# Comms.net
KiCad netlist of a schematic drawn in Altium Designer
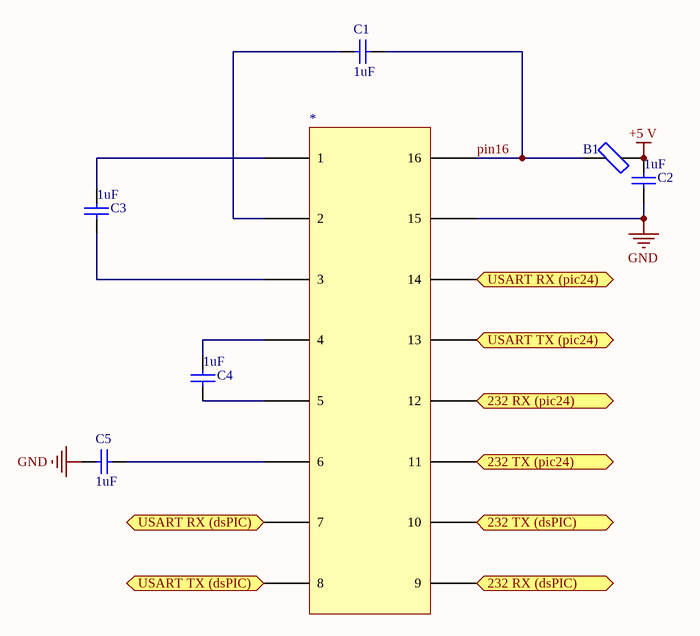
[diagram p0: Comms.SchDoc]

(export (version "E")
  (design (tool "Eeschema 10.0.6"))
  (components
    (comp (ref "*")
      (value "MAX232E")
      (footprint "SO-16_M")
      (libsource (lib "CustomParts_MattW") (part "max232"))
    )
    (comp (ref "B1")
      (value "Ferrite Bead")
      (footprint "Resistor 0603")
      (libsource (lib "PMUD") (part "Ferrite Bead"))
    )
    (comp (ref "C1")
      (value "1uF")
      (footprint "Capacitor 0603")
      (description "Capacitor (Semiconductor SIM Model)")
      (fields (field (name "Comment") "1uF Ceramic Low ESR") (field (name "PUBLISHER") "Altium Limited"))
      (libsource (lib "Miscellaneous Devices") (part "Cap Semi"))
    )
    (comp (ref "C2")
      (value "1uF")
      (footprint "Capacitor 0603")
      (description "Capacitor (Semiconductor SIM Model)")
      (fields (field (name "Comment") "1uF Ceramic Low ESR") (field (name "PUBLISHER") "Altium Limited"))
      (libsource (lib "Miscellaneous Devices") (part "Cap Semi"))
    )
    (comp (ref "C3")
      (value "1uF")
      (footprint "Capacitor 0603")
      (description "Capacitor (Semiconductor SIM Model)")
      (fields (field (name "Comment") "1uF Ceramic Low ESR") (field (name "PUBLISHER") "Altium Limited"))
      (libsource (lib "Miscellaneous Devices") (part "Cap Semi"))
    )
    (comp (ref "C4")
      (value "1uF")
      (footprint "Capacitor 0603")
      (description "Capacitor (Semiconductor SIM Model)")
      (fields (field (name "Comment") "1uF Ceramic Low ESR") (field (name "PUBLISHER") "Altium Limited"))
      (libsource (lib "Miscellaneous Devices") (part "Cap Semi"))
    )
    (comp (ref "C5")
      (value "1uF")
      (footprint "Capacitor 0603")
      (description "Capacitor (Semiconductor SIM Model)")
      (fields (field (name "Comment") "1uF Ceramic Low ESR") (field (name "PUBLISHER") "Altium Limited"))
      (libsource (lib "Miscellaneous Devices") (part "Cap Semi"))
    )
  )
  (nets
    (net (code "1") (name "+5 V") (class "Default")
      (node (ref "B1") (pin "1") (pinfunction "1_1") (pintype "passive"))
      (node (ref "C2") (pin "1") (pinfunction "1_1") (pintype "passive"))
    )
    (net (code "2") (name "/232 RX (dsPIC)") (class "Default")
      (node (ref "*") (pin "9") (pinfunction "9_9") (pintype "passive"))
    )
    (net (code "3") (name "/232 RX (pic24)") (class "Default")
      (node (ref "*") (pin "12") (pinfunction "12_12") (pintype "passive"))
    )
    (net (code "4") (name "/232 TX (dsPIC)") (class "Default")
      (node (ref "*") (pin "10") (pinfunction "10_10") (pintype "passive"))
    )
    (net (code "5") (name "/232 TX (pic24)") (class "Default")
      (node (ref "*") (pin "11") (pinfunction "11_11") (pintype "passive"))
    )
    (net (code "6") (name "/USART RX (dsPIC)") (class "Default")
      (node (ref "*") (pin "7") (pinfunction "7_7") (pintype "passive"))
    )
    (net (code "7") (name "/USART RX (pic24)") (class "Default")
      (node (ref "*") (pin "14") (pinfunction "14_14") (pintype "passive"))
    )
    (net (code "8") (name "/USART TX (dsPIC)") (class "Default")
      (node (ref "*") (pin "8") (pinfunction "8_8") (pintype "passive"))
    )
    (net (code "9") (name "/USART TX (pic24)") (class "Default")
      (node (ref "*") (pin "13") (pinfunction "13_13") (pintype "passive"))
    )
    (net (code "10") (name "/pin16") (class "Default")
      (node (ref "*") (pin "16") (pinfunction "16_16") (pintype "passive"))
      (node (ref "B1") (pin "2") (pinfunction "2_2") (pintype "passive"))
      (node (ref "C1") (pin "2") (pinfunction "2_2") (pintype "passive"))
    )
    (net (code "11") (name "GND") (class "Default")
      (node (ref "*") (pin "15") (pinfunction "15_15") (pintype "passive"))
      (node (ref "C2") (pin "2") (pinfunction "2_2") (pintype "passive"))
      (node (ref "C5") (pin "1") (pinfunction "1_1") (pintype "passive"))
    )
    (net (code "12") (name "Net-(*-Pad1)") (class "Default")
      (node (ref "*") (pin "1") (pinfunction "1_1") (pintype "passive"))
      (node (ref "C3") (pin "1") (pinfunction "1_1") (pintype "passive"))
    )
    (net (code "13") (name "Net-(*-Pad2)") (class "Default")
      (node (ref "*") (pin "2") (pinfunction "2_2") (pintype "passive"))
      (node (ref "C1") (pin "1") (pinfunction "1_1") (pintype "passive"))
    )
    (net (code "14") (name "Net-(*-Pad3)") (class "Default")
      (node (ref "*") (pin "3") (pinfunction "3_3") (pintype "passive"))
      (node (ref "C3") (pin "2") (pinfunction "2_2") (pintype "passive"))
    )
    (net (code "15") (name "Net-(*-Pad4)") (class "Default")
      (node (ref "*") (pin "4") (pinfunction "4_4") (pintype "passive"))
      (node (ref "C4") (pin "1") (pinfunction "1_1") (pintype "passive"))
    )
    (net (code "16") (name "Net-(*-Pad5)") (class "Default")
      (node (ref "*") (pin "5") (pinfunction "5_5") (pintype "passive"))
      (node (ref "C4") (pin "2") (pinfunction "2_2") (pintype "passive"))
    )
    (net (code "17") (name "Net-(*-Pad6)") (class "Default")
      (node (ref "*") (pin "6") (pinfunction "6_6") (pintype "passive"))
      (node (ref "C5") (pin "2") (pinfunction "2_2") (pintype "passive"))
    )
  )
)
